# breakout_ble113.net
KiCad netlist of a schematic drawn in EAGLE
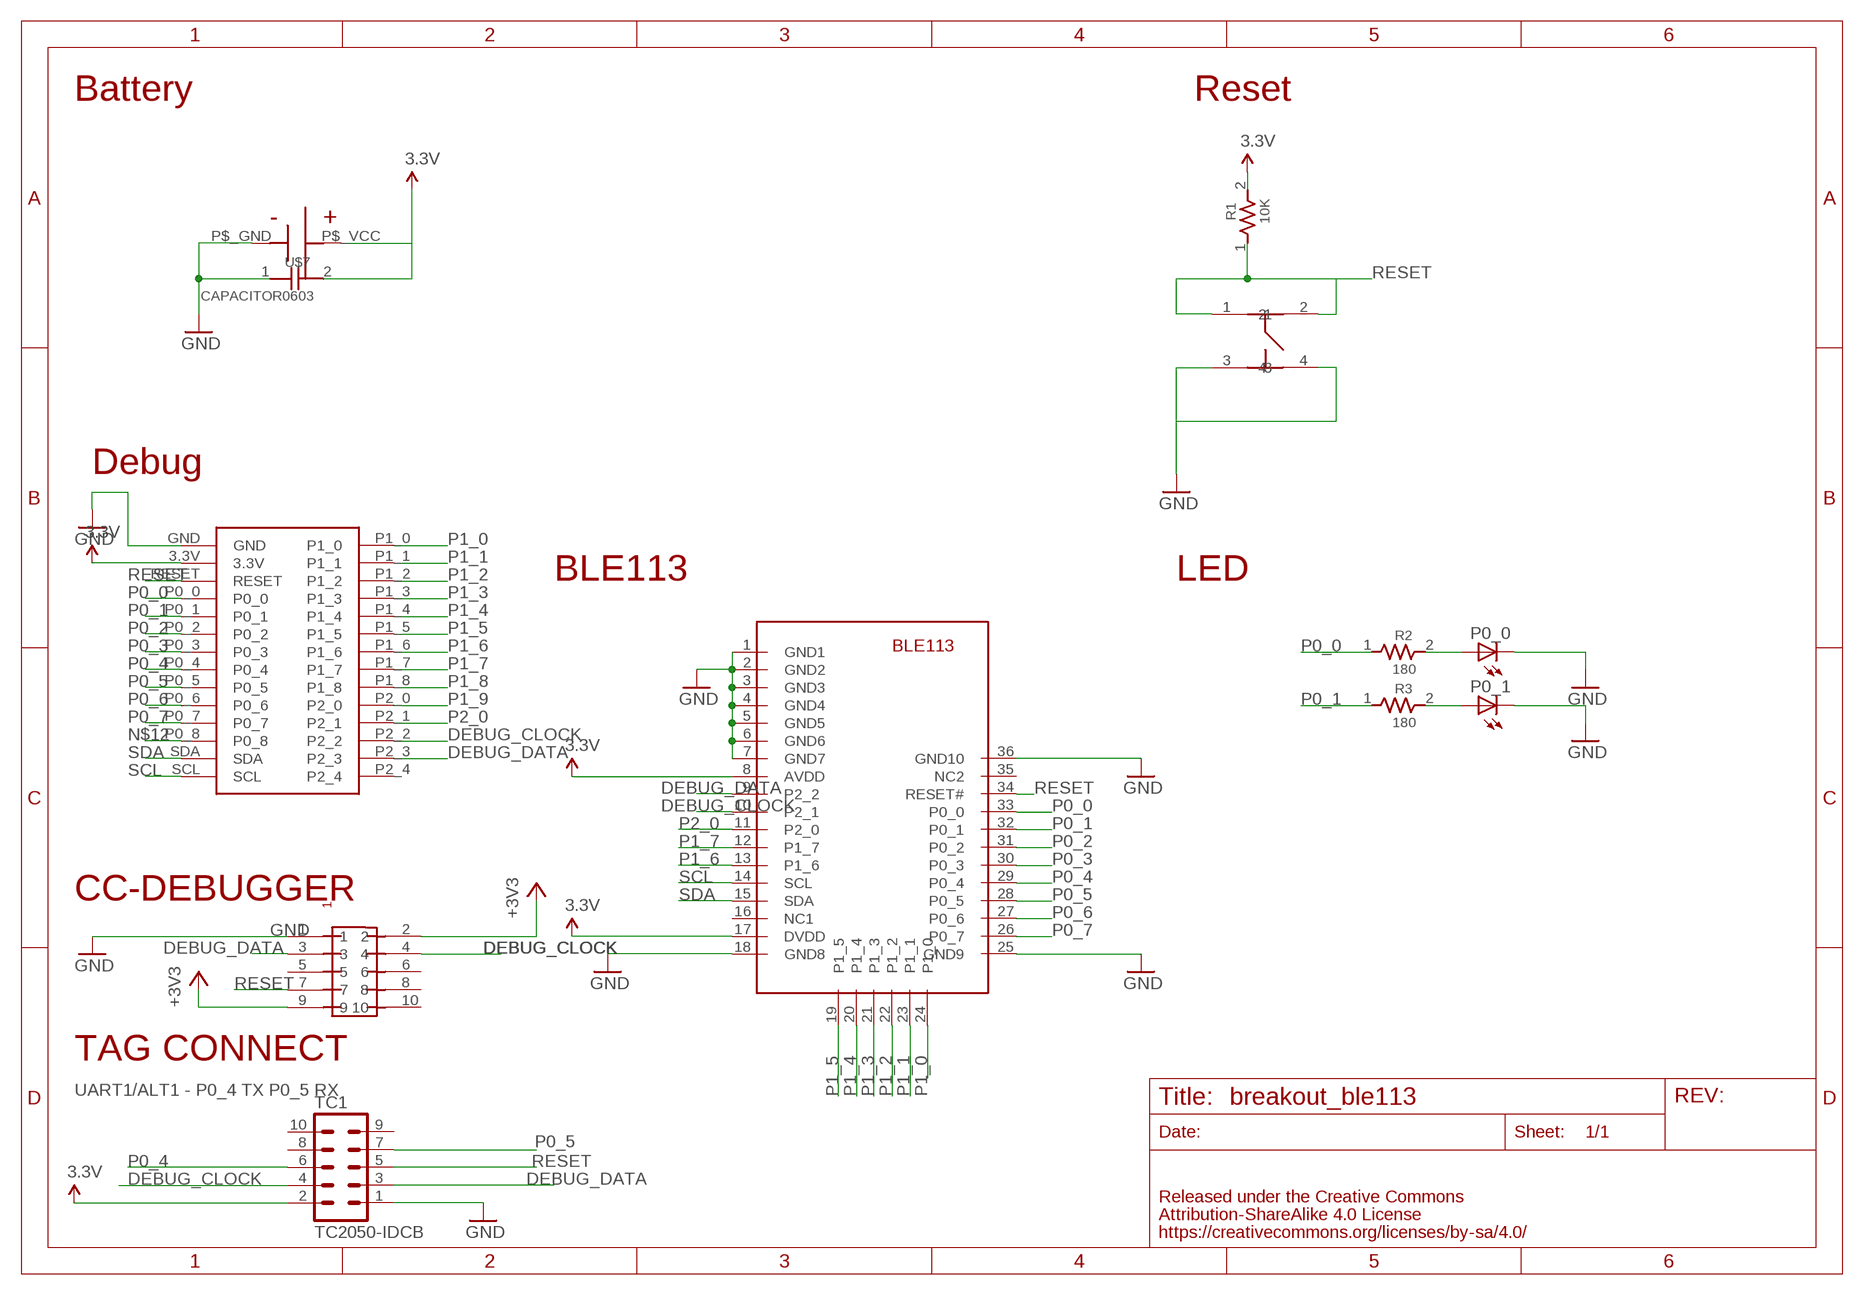
[diagram p0: schematic, sheet 1]

(export (version "E")
  (design (tool "Eeschema 10.0.6"))
  (components
    (comp (ref "P0_0")
      (value "LEDCHIP-LED0603")
      (footprint "eagle-import:CHIP-LED0603")
      (libsource (lib "eagle-import") (part "LEDCHIP-LED0603"))
    )
    (comp (ref "P0_1")
      (value "LEDCHIP-LED0603")
      (footprint "eagle-import:CHIP-LED0603")
      (libsource (lib "eagle-import") (part "LEDCHIP-LED0603"))
    )
    (comp (ref "R1")
      (value "10K")
      (footprint "eagle-import:0603")
      (libsource (lib "eagle-import") (part "RESISTOR0603"))
    )
    (comp (ref "R2")
      (value "180")
      (footprint "eagle-import:0603")
      (libsource (lib "eagle-import") (part "RESISTOR0603"))
    )
    (comp (ref "R3")
      (value "180")
      (footprint "eagle-import:0603")
      (libsource (lib "eagle-import") (part "RESISTOR0603"))
    )
    (comp (ref "TC1")
      (value "TC2050-IDCB")
      (footprint "eagle-import:TC2050-IDC")
      (libsource (lib "eagle-import") (part "TC2050-IDCB"))
    )
    (comp (ref "U$1")
      (value "PIN-HEADER-SMT(1.27MM)2X5")
      (footprint "eagle-import:PIN-HEADER-SMT(1.27MM)2X5")
      (libsource (lib "eagle-import") (part "PIN-HEADER-SMT(1.27MM)2X5"))
    )
    (comp (ref "U$2")
      (value "BREAKOUT_BLE")
      (footprint "eagle-import:BREAKOUT_BLE")
      (libsource (lib "eagle-import") (part "BREAKOUT_BLE"))
    )
    (comp (ref "U$3")
      (value "BLUEGIGA-BLE113")
      (footprint "eagle-import:BLUEGIGA-BLE113")
      (libsource (lib "eagle-import") (part "BLUEGIGA-BLE113"))
    )
    (comp (ref "U$4")
      (value "SMTU2450-TOP")
      (footprint "eagle-import:SMTU2450")
      (libsource (lib "eagle-import") (part "SMTU2450-TOP"))
    )
    (comp (ref "U$5")
      (value "SWICTH-4P(KMR2)")
      (footprint "eagle-import:SWITCH-4P(KMR2)")
      (libsource (lib "eagle-import") (part "SWICTH-4P(KMR2)"))
    )
    (comp (ref "U$7")
      (value "CAPACITOR0603")
      (footprint "eagle-import:0603")
      (libsource (lib "eagle-import") (part "CAPACITOR0603"))
    )
  )
  (nets
    (net (code "1") (name "+3V3") (class "Default")
      (node (ref "U$1") (pin "2") (pinfunction "2_2") (pintype "bidirectional"))
      (node (ref "U$1") (pin "9") (pinfunction "9_9") (pintype "bidirectional"))
    )
    (net (code "2") (name "/DEBUG_CLOCK") (class "Default")
      (node (ref "TC1") (pin "4") (pinfunction "4_4") (pintype "passive"))
      (node (ref "U$1") (pin "4") (pinfunction "4_4") (pintype "bidirectional"))
      (node (ref "U$2") (pin "P2_2") (pinfunction "P2_2_P2_2") (pintype "bidirectional"))
      (node (ref "U$3") (pin "10") (pinfunction "P2_1_10") (pintype "bidirectional"))
    )
    (net (code "3") (name "/DEBUG_DATA") (class "Default")
      (node (ref "TC1") (pin "3") (pinfunction "3_3") (pintype "passive"))
      (node (ref "U$1") (pin "3") (pinfunction "3_3") (pintype "bidirectional"))
      (node (ref "U$2") (pin "P2_3") (pinfunction "P2_3_P2_3") (pintype "bidirectional"))
      (node (ref "U$3") (pin "9") (pinfunction "P2_2_9") (pintype "bidirectional"))
    )
    (net (code "4") (name "/N$12") (class "Default")
      (node (ref "U$2") (pin "P0_8") (pinfunction "P0_8_P0_8") (pintype "bidirectional"))
    )
    (net (code "5") (name "/P0_0") (class "Default")
      (node (ref "R2") (pin "1") (pinfunction "1_1") (pintype "passive"))
      (node (ref "U$2") (pin "P0_0") (pinfunction "P0_0_P0_0") (pintype "bidirectional"))
      (node (ref "U$3") (pin "33") (pinfunction "P0_0_33") (pintype "bidirectional"))
    )
    (net (code "6") (name "/P0_1") (class "Default")
      (node (ref "R3") (pin "1") (pinfunction "1_1") (pintype "passive"))
      (node (ref "U$2") (pin "P0_1") (pinfunction "P0_1_P0_1") (pintype "bidirectional"))
      (node (ref "U$3") (pin "32") (pinfunction "P0_1_32") (pintype "bidirectional"))
    )
    (net (code "7") (name "/P0_2") (class "Default")
      (node (ref "U$2") (pin "P0_2") (pinfunction "P0_2_P0_2") (pintype "bidirectional"))
      (node (ref "U$3") (pin "31") (pinfunction "P0_2_31") (pintype "bidirectional"))
    )
    (net (code "8") (name "/P0_3") (class "Default")
      (node (ref "U$2") (pin "P0_3") (pinfunction "P0_3_P0_3") (pintype "bidirectional"))
      (node (ref "U$3") (pin "30") (pinfunction "P0_3_30") (pintype "bidirectional"))
    )
    (net (code "9") (name "/P0_4") (class "Default")
      (node (ref "TC1") (pin "6") (pinfunction "6_6") (pintype "passive"))
      (node (ref "U$2") (pin "P0_4") (pinfunction "P0_4_P0_4") (pintype "bidirectional"))
      (node (ref "U$3") (pin "29") (pinfunction "P0_4_29") (pintype "bidirectional"))
    )
    (net (code "10") (name "/P0_5") (class "Default")
      (node (ref "TC1") (pin "7") (pinfunction "7_7") (pintype "passive"))
      (node (ref "U$2") (pin "P0_5") (pinfunction "P0_5_P0_5") (pintype "bidirectional"))
      (node (ref "U$3") (pin "28") (pinfunction "P0_5_28") (pintype "bidirectional"))
    )
    (net (code "11") (name "/P0_6") (class "Default")
      (node (ref "U$2") (pin "P0_6") (pinfunction "P0_6_P0_6") (pintype "bidirectional"))
      (node (ref "U$3") (pin "27") (pinfunction "P0_6_27") (pintype "bidirectional"))
    )
    (net (code "12") (name "/P0_7") (class "Default")
      (node (ref "U$2") (pin "P0_7") (pinfunction "P0_7_P0_7") (pintype "bidirectional"))
      (node (ref "U$3") (pin "26") (pinfunction "P0_7_26") (pintype "bidirectional"))
    )
    (net (code "13") (name "/P1_0") (class "Default")
      (node (ref "U$2") (pin "P1_0") (pinfunction "P1_0_P1_0") (pintype "bidirectional"))
      (node (ref "U$3") (pin "24") (pinfunction "P1_0_24") (pintype "bidirectional"))
    )
    (net (code "14") (name "/P1_1") (class "Default")
      (node (ref "U$2") (pin "P1_1") (pinfunction "P1_1_P1_1") (pintype "bidirectional"))
      (node (ref "U$3") (pin "23") (pinfunction "P1_1_23") (pintype "bidirectional"))
    )
    (net (code "15") (name "/P1_2") (class "Default")
      (node (ref "U$2") (pin "P1_2") (pinfunction "P1_2_P1_2") (pintype "bidirectional"))
      (node (ref "U$3") (pin "22") (pinfunction "P1_2_22") (pintype "bidirectional"))
    )
    (net (code "16") (name "/P1_3") (class "Default")
      (node (ref "U$2") (pin "P1_3") (pinfunction "P1_3_P1_3") (pintype "bidirectional"))
      (node (ref "U$3") (pin "21") (pinfunction "P1_3_21") (pintype "bidirectional"))
    )
    (net (code "17") (name "/P1_4") (class "Default")
      (node (ref "U$2") (pin "P1_4") (pinfunction "P1_4_P1_4") (pintype "bidirectional"))
      (node (ref "U$3") (pin "20") (pinfunction "P1_4_20") (pintype "bidirectional"))
    )
    (net (code "18") (name "/P1_5") (class "Default")
      (node (ref "U$2") (pin "P1_5") (pinfunction "P1_5_P1_5") (pintype "bidirectional"))
      (node (ref "U$3") (pin "19") (pinfunction "P1_5_19") (pintype "bidirectional"))
    )
    (net (code "19") (name "/P1_6") (class "Default")
      (node (ref "U$2") (pin "P1_6") (pinfunction "P1_6_P1_6") (pintype "bidirectional"))
      (node (ref "U$3") (pin "13") (pinfunction "P1_6_13") (pintype "bidirectional"))
    )
    (net (code "20") (name "/P1_7") (class "Default")
      (node (ref "U$2") (pin "P1_7") (pinfunction "P1_7_P1_7") (pintype "bidirectional"))
      (node (ref "U$3") (pin "12") (pinfunction "P1_7_12") (pintype "bidirectional"))
    )
    (net (code "21") (name "/P1_8") (class "Default")
      (node (ref "U$2") (pin "P1_8") (pinfunction "P1_8_P1_8") (pintype "bidirectional"))
    )
    (net (code "22") (name "/P1_9") (class "Default")
      (node (ref "U$2") (pin "P2_0") (pinfunction "P2_0_P2_0") (pintype "bidirectional"))
    )
    (net (code "23") (name "/P2_0") (class "Default")
      (node (ref "U$2") (pin "P2_1") (pinfunction "P2_1_P2_1") (pintype "bidirectional"))
      (node (ref "U$3") (pin "11") (pinfunction "P2_0_11") (pintype "bidirectional"))
    )
    (net (code "24") (name "/RESET") (class "Default")
      (node (ref "R1") (pin "1") (pinfunction "1_1") (pintype "passive"))
      (node (ref "TC1") (pin "5") (pinfunction "5_5") (pintype "passive"))
      (node (ref "U$1") (pin "7") (pinfunction "7_7") (pintype "bidirectional"))
      (node (ref "U$2") (pin "RESET") (pinfunction "RESET_RESET") (pintype "bidirectional"))
      (node (ref "U$3") (pin "34") (pinfunction "RESET#_34") (pintype "bidirectional"))
      (node (ref "U$5") (pin "1") (pinfunction "1_1") (pintype "bidirectional"))
      (node (ref "U$5") (pin "2") (pinfunction "2_2") (pintype "bidirectional"))
    )
    (net (code "25") (name "/SCL") (class "Default")
      (node (ref "U$2") (pin "SCL") (pinfunction "SCL_SCL") (pintype "bidirectional"))
      (node (ref "U$3") (pin "14") (pinfunction "SCL_14") (pintype "bidirectional"))
    )
    (net (code "26") (name "/SDA") (class "Default")
      (node (ref "U$2") (pin "SDA") (pinfunction "SDA_SDA") (pintype "bidirectional"))
      (node (ref "U$3") (pin "15") (pinfunction "SDA_15") (pintype "bidirectional"))
    )
    (net (code "27") (name "3.3V") (class "Default")
      (node (ref "R1") (pin "2") (pinfunction "2_2") (pintype "passive"))
      (node (ref "TC1") (pin "2") (pinfunction "2_2") (pintype "passive"))
      (node (ref "U$2") (pin "3.3V") (pinfunction "3.3V_3.3V") (pintype "bidirectional"))
      (node (ref "U$3") (pin "17") (pinfunction "DVDD_17") (pintype "bidirectional"))
      (node (ref "U$3") (pin "8") (pinfunction "AVDD_8") (pintype "bidirectional"))
      (node (ref "U$4") (pin "P$_VCC") (pinfunction "+_P$_VCC") (pintype "bidirectional"))
      (node (ref "U$7") (pin "2") (pinfunction "2_2") (pintype "passive"))
    )
    (net (code "28") (name "GND") (class "Default")
      (node (ref "P0_0") (pin "C") (pinfunction "C_C") (pintype "passive"))
      (node (ref "P0_1") (pin "C") (pinfunction "C_C") (pintype "passive"))
      (node (ref "TC1") (pin "1") (pinfunction "1_1") (pintype "passive"))
      (node (ref "U$1") (pin "1") (pinfunction "1_1") (pintype "bidirectional"))
      (node (ref "U$2") (pin "GND") (pinfunction "GND_GND") (pintype "bidirectional"))
      (node (ref "U$3") (pin "1") (pinfunction "GND1_1") (pintype "bidirectional"))
      (node (ref "U$3") (pin "18") (pinfunction "GND8_18") (pintype "bidirectional"))
      (node (ref "U$3") (pin "2") (pinfunction "GND2_2") (pintype "bidirectional"))
      (node (ref "U$3") (pin "25") (pinfunction "GND9_25") (pintype "bidirectional"))
      (node (ref "U$3") (pin "3") (pinfunction "GND3_3") (pintype "bidirectional"))
      (node (ref "U$3") (pin "36") (pinfunction "GND10_36") (pintype "bidirectional"))
      (node (ref "U$3") (pin "4") (pinfunction "GND4_4") (pintype "bidirectional"))
      (node (ref "U$3") (pin "5") (pinfunction "GND5_5") (pintype "bidirectional"))
      (node (ref "U$3") (pin "6") (pinfunction "GND6_6") (pintype "bidirectional"))
      (node (ref "U$3") (pin "7") (pinfunction "GND7_7") (pintype "bidirectional"))
      (node (ref "U$4") (pin "P$_GND") (pinfunction "-_P$_GND") (pintype "bidirectional"))
      (node (ref "U$5") (pin "3") (pinfunction "3_3") (pintype "bidirectional"))
      (node (ref "U$5") (pin "4") (pinfunction "4_4") (pintype "bidirectional"))
      (node (ref "U$7") (pin "1") (pinfunction "1_1") (pintype "passive"))
    )
    (net (code "29") (name "Net-(P0_0-PadA)") (class "Default")
      (node (ref "P0_0") (pin "A") (pinfunction "A_A") (pintype "passive"))
      (node (ref "R2") (pin "2") (pinfunction "2_2") (pintype "passive"))
    )
    (net (code "30") (name "Net-(P0_1-PadA)") (class "Default")
      (node (ref "P0_1") (pin "A") (pinfunction "A_A") (pintype "passive"))
      (node (ref "R3") (pin "2") (pinfunction "2_2") (pintype "passive"))
    )
    (net (code "31") (name "unconnected-(TC1-Pad8)") (class "Default")
      (node (ref "TC1") (pin "8") (pinfunction "8_8") (pintype "passive"))
    )
    (net (code "32") (name "unconnected-(TC1-Pad9)") (class "Default")
      (node (ref "TC1") (pin "9") (pinfunction "9_9") (pintype "passive"))
    )
    (net (code "33") (name "unconnected-(TC1-Pad10)") (class "Default")
      (node (ref "TC1") (pin "10") (pinfunction "10_10") (pintype "passive"))
    )
    (net (code "34") (name "unconnected-(U$1-Pad5)") (class "Default")
      (node (ref "U$1") (pin "5") (pinfunction "5_5") (pintype "bidirectional"))
    )
    (net (code "35") (name "unconnected-(U$1-Pad6)") (class "Default")
      (node (ref "U$1") (pin "6") (pinfunction "6_6") (pintype "bidirectional"))
    )
    (net (code "36") (name "unconnected-(U$1-Pad8)") (class "Default")
      (node (ref "U$1") (pin "8") (pinfunction "8_8") (pintype "bidirectional"))
    )
    (net (code "37") (name "unconnected-(U$1-Pad10)") (class "Default")
      (node (ref "U$1") (pin "10") (pinfunction "10_10") (pintype "bidirectional"))
    )
    (net (code "38") (name "unconnected-(U$2-PadP2_4)") (class "Default")
      (node (ref "U$2") (pin "P2_4") (pinfunction "P2_4_P2_4") (pintype "bidirectional"))
    )
    (net (code "39") (name "unconnected-(U$3-NC1-Pad16)") (class "Default")
      (node (ref "U$3") (pin "16") (pinfunction "NC1_16") (pintype "bidirectional"))
    )
    (net (code "40") (name "unconnected-(U$3-NC2-Pad35)") (class "Default")
      (node (ref "U$3") (pin "35") (pinfunction "NC2_35") (pintype "bidirectional"))
    )
  )
)
